# usb_sniffer.net
KiCad netlist of a schematic drawn in EAGLE
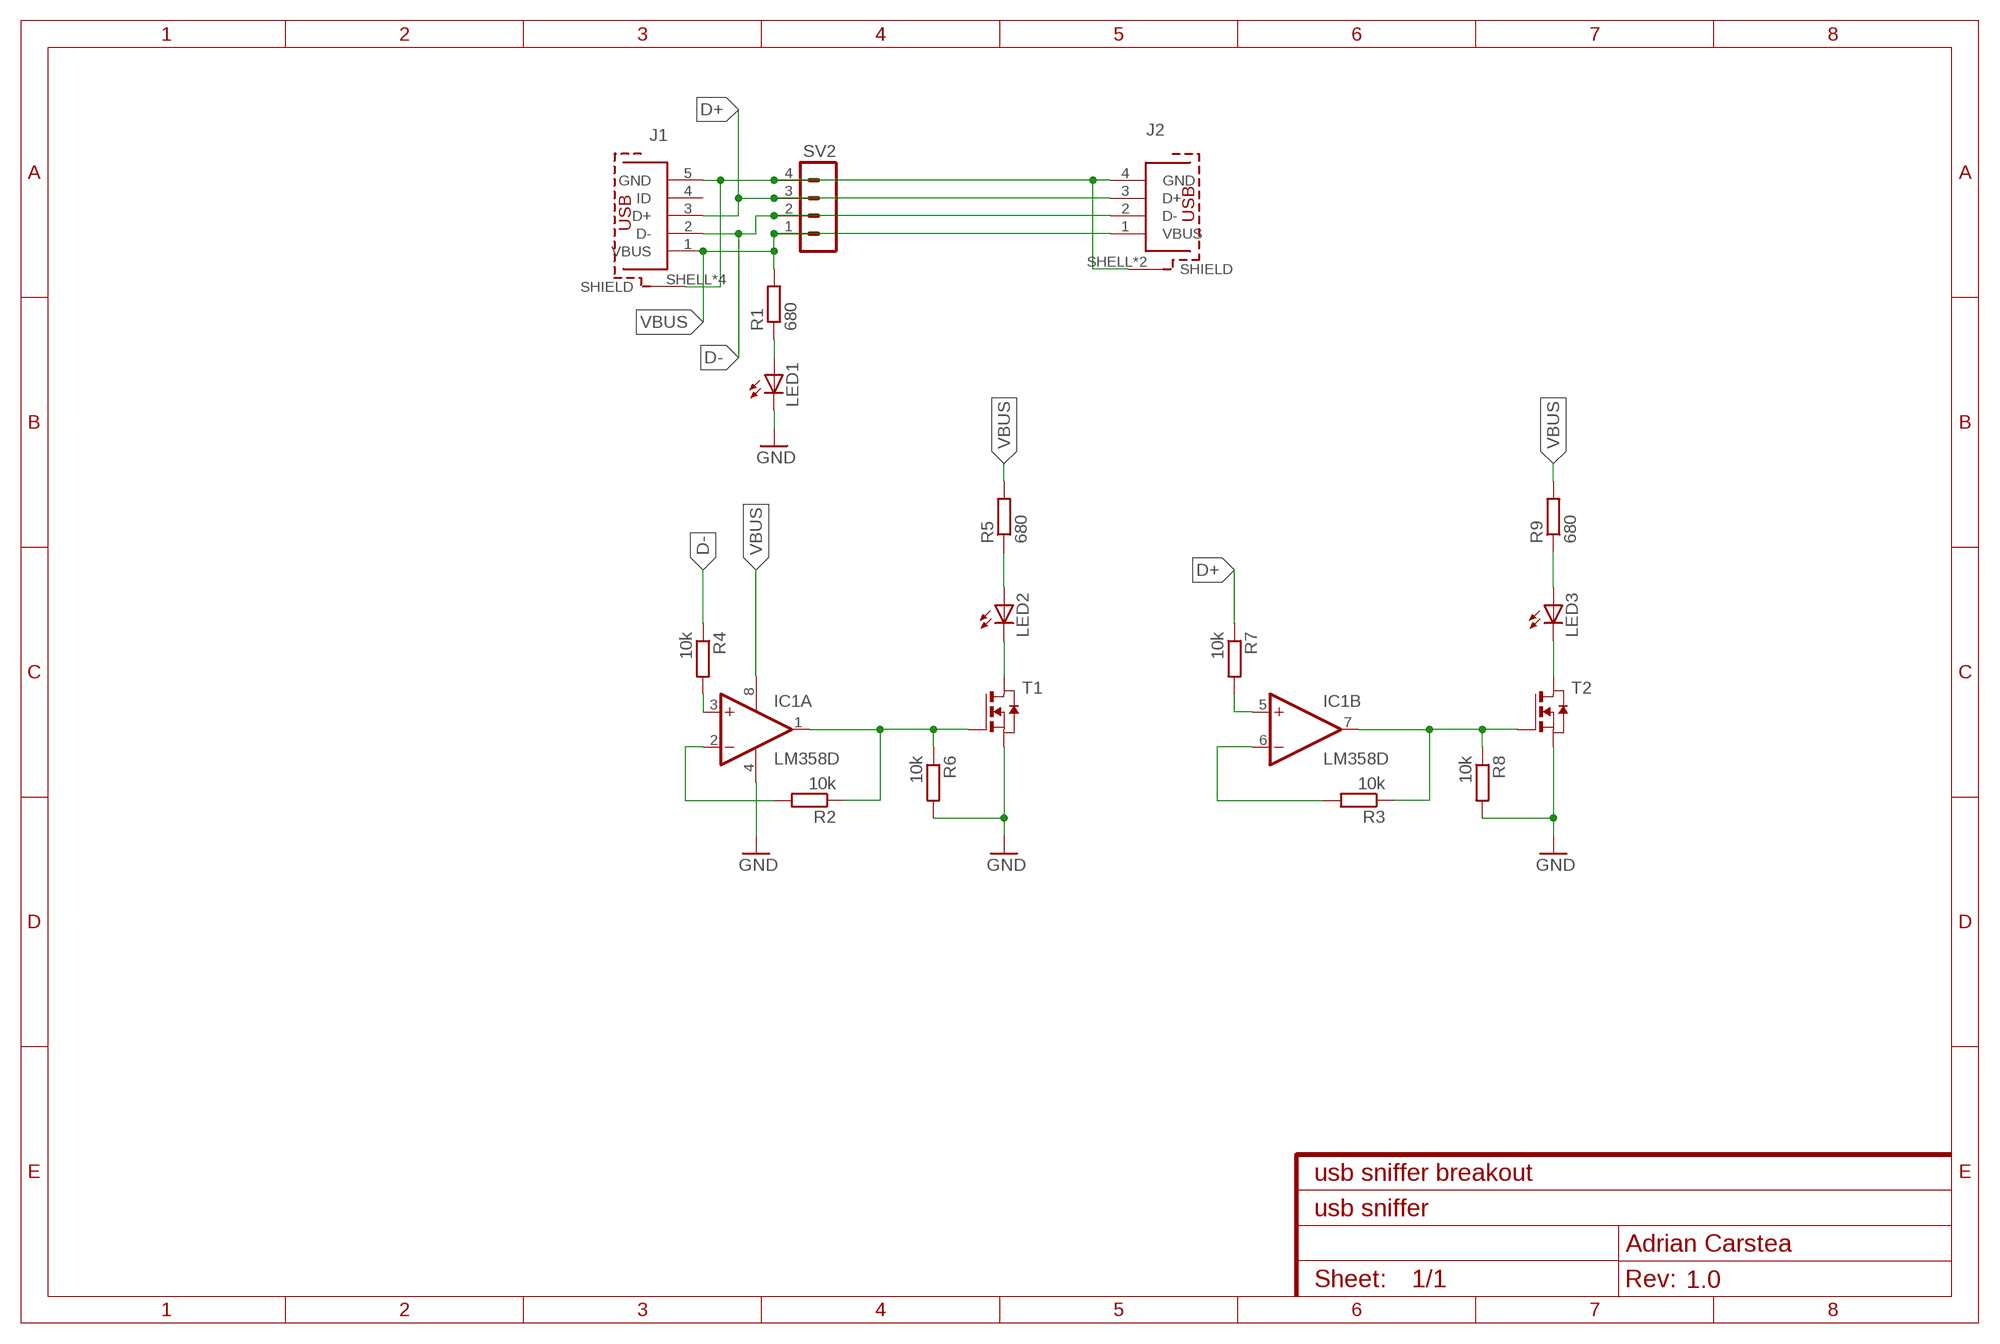
[diagram p0: schematic, sheet 1]

(export (version "E")
  (design (tool "Eeschema 10.0.6"))
  (components
    (comp (ref "IC1")
      (value "LM358D")
      (footprint "eagle-import:SO08")
      (libsource (lib "eagle-import") (part "LM358D"))
    )
    (comp (ref "J1")
      (value "629105136821")
      (footprint "eagle-import:629105136821")
      (libsource (lib "eagle-import") (part "629105136821"))
    )
    (comp (ref "J2")
      (value "61400416021")
      (footprint "eagle-import:61400416021")
      (libsource (lib "eagle-import") (part "61400416021"))
    )
    (comp (ref "LED1")
      (value "LEDSML0805")
      (footprint "eagle-import:SML0805")
      (libsource (lib "eagle-import") (part "LEDSML0805"))
    )
    (comp (ref "LED2")
      (value "LEDSML0805")
      (footprint "eagle-import:SML0805")
      (libsource (lib "eagle-import") (part "LEDSML0805"))
    )
    (comp (ref "LED3")
      (value "LEDSML0805")
      (footprint "eagle-import:SML0805")
      (libsource (lib "eagle-import") (part "LEDSML0805"))
    )
    (comp (ref "R1")
      (value "680")
      (footprint "eagle-import:R0805")
      (libsource (lib "eagle-import") (part "R-EU_R0805"))
    )
    (comp (ref "R2")
      (value "10k")
      (footprint "eagle-import:R0805")
      (libsource (lib "eagle-import") (part "R-EU_R0805"))
    )
    (comp (ref "R3")
      (value "10k")
      (footprint "eagle-import:R0805")
      (libsource (lib "eagle-import") (part "R-EU_R0805"))
    )
    (comp (ref "R4")
      (value "10k")
      (footprint "eagle-import:R0805")
      (libsource (lib "eagle-import") (part "R-EU_R0805"))
    )
    (comp (ref "R5")
      (value "680")
      (footprint "eagle-import:R0805")
      (libsource (lib "eagle-import") (part "R-EU_R0805"))
    )
    (comp (ref "R6")
      (value "10k")
      (footprint "eagle-import:R0805")
      (libsource (lib "eagle-import") (part "R-EU_R0805"))
    )
    (comp (ref "R7")
      (value "10k")
      (footprint "eagle-import:R0805")
      (libsource (lib "eagle-import") (part "R-EU_R0805"))
    )
    (comp (ref "R8")
      (value "10k")
      (footprint "eagle-import:R0805")
      (libsource (lib "eagle-import") (part "R-EU_R0805"))
    )
    (comp (ref "R9")
      (value "680")
      (footprint "eagle-import:R0805")
      (libsource (lib "eagle-import") (part "R-EU_R0805"))
    )
    (comp (ref "SV2")
      (value "MA04-1")
      (footprint "eagle-import:MA04-1")
      (libsource (lib "eagle-import") (part "MA04-1"))
    )
    (comp (ref "T1")
      (value "NMOSSOT23")
      (footprint "eagle-import:SOT-23")
      (libsource (lib "eagle-import") (part "NMOSSOT23"))
    )
    (comp (ref "T2")
      (value "NMOSSOT23")
      (footprint "eagle-import:SOT-23")
      (libsource (lib "eagle-import") (part "NMOSSOT23"))
    )
  )
  (nets
    (net (code "1") (name "D+") (class "Default")
      (node (ref "J1") (pin "3") (pinfunction "D+_3") (pintype "passive"))
      (node (ref "J2") (pin "3") (pinfunction "D+_3") (pintype "bidirectional"))
      (node (ref "R7") (pin "1") (pinfunction "1_1") (pintype "passive"))
      (node (ref "SV2") (pin "3") (pinfunction "3_3") (pintype "passive"))
    )
    (net (code "2") (name "D-") (class "Default")
      (node (ref "J1") (pin "2") (pinfunction "D-_2") (pintype "passive"))
      (node (ref "J2") (pin "2") (pinfunction "D-_2") (pintype "bidirectional"))
      (node (ref "R4") (pin "1") (pinfunction "1_1") (pintype "passive"))
      (node (ref "SV2") (pin "2") (pinfunction "2_2") (pintype "passive"))
    )
    (net (code "3") (name "GND") (class "Default")
      (node (ref "IC1") (pin "4") (pinfunction "V-_4") (pintype "power_in"))
      (node (ref "J1") (pin "5") (pinfunction "GND_5") (pintype "passive"))
      (node (ref "J1") (pin "SHELL") (pinfunction "SHIELD_SHELL") (pintype "passive"))
      (node (ref "J1") (pin "SHELL1") (pinfunction "SHIELD_SHELL1") (pintype "passive"))
      (node (ref "J1") (pin "SHELL2") (pinfunction "SHIELD_SHELL2") (pintype "passive"))
      (node (ref "J1") (pin "SHELL3") (pinfunction "SHIELD_SHELL3") (pintype "passive"))
      (node (ref "J2") (pin "4") (pinfunction "GND_4") (pintype "bidirectional"))
      (node (ref "J2") (pin "SHELL") (pinfunction "SHIELD_SHELL") (pintype "bidirectional"))
      (node (ref "J2") (pin "SHELL1") (pinfunction "SHIELD_SHELL1") (pintype "bidirectional"))
      (node (ref "LED1") (pin "C") (pinfunction "C_C") (pintype "passive"))
      (node (ref "R6") (pin "2") (pinfunction "2_2") (pintype "passive"))
      (node (ref "R8") (pin "2") (pinfunction "2_2") (pintype "passive"))
      (node (ref "SV2") (pin "4") (pinfunction "4_4") (pintype "passive"))
      (node (ref "T1") (pin "2") (pinfunction "S_2") (pintype "passive"))
      (node (ref "T2") (pin "2") (pinfunction "S_2") (pintype "passive"))
    )
    (net (code "4") (name "Net-(IC1A-+IN)") (class "Default")
      (node (ref "IC1") (pin "3") (pinfunction "+IN_3") (pintype "input"))
      (node (ref "R4") (pin "2") (pinfunction "2_2") (pintype "passive"))
    )
    (net (code "5") (name "Net-(IC1A--IN)") (class "Default")
      (node (ref "IC1") (pin "2") (pinfunction "-IN_2") (pintype "input"))
      (node (ref "R2") (pin "2") (pinfunction "2_2") (pintype "passive"))
    )
    (net (code "6") (name "Net-(IC1A-OUT)") (class "Default")
      (node (ref "IC1") (pin "1") (pinfunction "OUT_1") (pintype "output"))
      (node (ref "R2") (pin "1") (pinfunction "1_1") (pintype "passive"))
      (node (ref "R6") (pin "1") (pinfunction "1_1") (pintype "passive"))
      (node (ref "T1") (pin "3") (pinfunction "G_3") (pintype "passive"))
    )
    (net (code "7") (name "Net-(IC1B-+IN)") (class "Default")
      (node (ref "IC1") (pin "5") (pinfunction "+IN_5") (pintype "input"))
      (node (ref "R7") (pin "2") (pinfunction "2_2") (pintype "passive"))
    )
    (net (code "8") (name "Net-(IC1B--IN)") (class "Default")
      (node (ref "IC1") (pin "6") (pinfunction "-IN_6") (pintype "input"))
      (node (ref "R3") (pin "2") (pinfunction "2_2") (pintype "passive"))
    )
    (net (code "9") (name "Net-(IC1B-OUT)") (class "Default")
      (node (ref "IC1") (pin "7") (pinfunction "OUT_7") (pintype "output"))
      (node (ref "R3") (pin "1") (pinfunction "1_1") (pintype "passive"))
      (node (ref "R8") (pin "1") (pinfunction "1_1") (pintype "passive"))
      (node (ref "T2") (pin "3") (pinfunction "G_3") (pintype "passive"))
    )
    (net (code "10") (name "Net-(LED1-PadA)") (class "Default")
      (node (ref "LED1") (pin "A") (pinfunction "A_A") (pintype "passive"))
      (node (ref "R1") (pin "1") (pinfunction "1_1") (pintype "passive"))
    )
    (net (code "11") (name "Net-(LED2-PadA)") (class "Default")
      (node (ref "LED2") (pin "A") (pinfunction "A_A") (pintype "passive"))
      (node (ref "R5") (pin "1") (pinfunction "1_1") (pintype "passive"))
    )
    (net (code "12") (name "Net-(LED3-PadA)") (class "Default")
      (node (ref "LED3") (pin "A") (pinfunction "A_A") (pintype "passive"))
      (node (ref "R9") (pin "1") (pinfunction "1_1") (pintype "passive"))
    )
    (net (code "13") (name "Net-(T1-D)") (class "Default")
      (node (ref "LED2") (pin "C") (pinfunction "C_C") (pintype "passive"))
      (node (ref "T1") (pin "1") (pinfunction "D_1") (pintype "passive"))
    )
    (net (code "14") (name "Net-(T2-D)") (class "Default")
      (node (ref "LED3") (pin "C") (pinfunction "C_C") (pintype "passive"))
      (node (ref "T2") (pin "1") (pinfunction "D_1") (pintype "passive"))
    )
    (net (code "15") (name "VBUS") (class "Default")
      (node (ref "IC1") (pin "8") (pinfunction "V+_8") (pintype "power_in"))
      (node (ref "J1") (pin "1") (pinfunction "VBUS_1") (pintype "passive"))
      (node (ref "J2") (pin "1") (pinfunction "VBUS_1") (pintype "bidirectional"))
      (node (ref "R1") (pin "2") (pinfunction "2_2") (pintype "passive"))
      (node (ref "R5") (pin "2") (pinfunction "2_2") (pintype "passive"))
      (node (ref "R9") (pin "2") (pinfunction "2_2") (pintype "passive"))
      (node (ref "SV2") (pin "1") (pinfunction "1_1") (pintype "passive"))
    )
    (net (code "16") (name "unconnected-(J1-ID-Pad4)") (class "Default")
      (node (ref "J1") (pin "4") (pinfunction "ID_4") (pintype "passive"))
    )
  )
)
